# TASR1000.net
KiCad netlist of a schematic drawn in Altium Designer
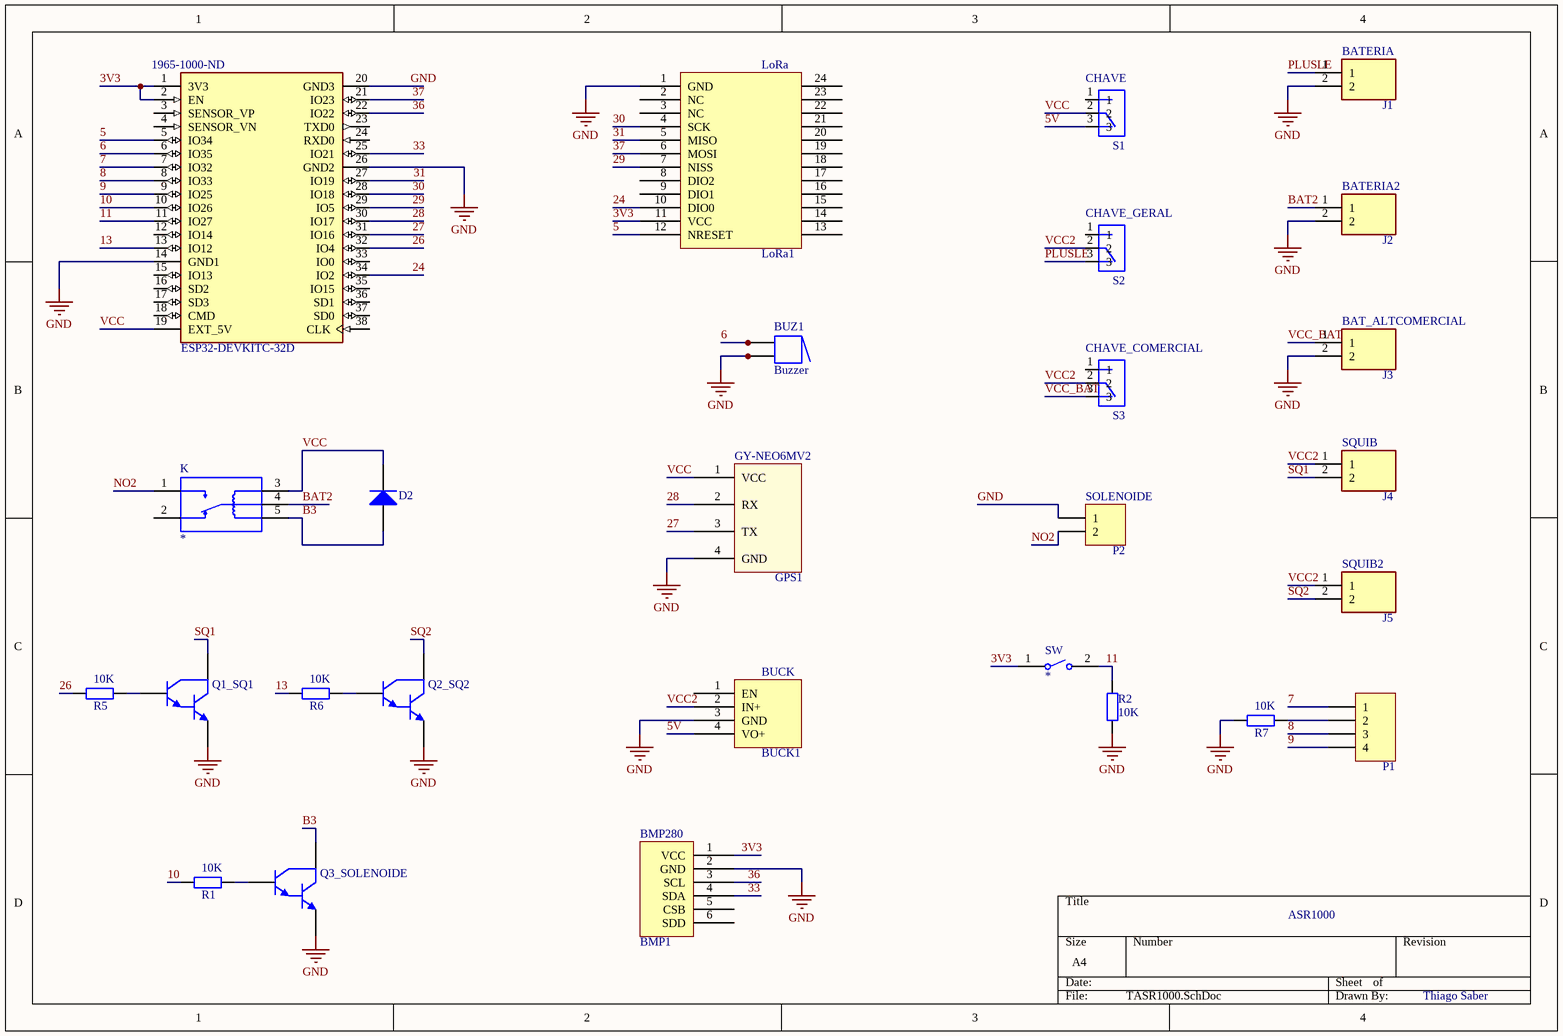
[diagram p0: TASR1000.SchDoc]

(export (version "E")
  (design (tool "Eeschema 10.0.6"))
  (components
    (comp (ref "BMP1")
      (value "BMP280")
      (footprint "BMP280")
      (description "BMP280 usado no projeto ASR1000.")
      (libsource (lib "BibliotecaASR1000") (part "BMP280"))
    )
    (comp (ref "BUCK1")
      (value "Buck")
      (footprint "BUCK")
      (description "Buck usado no projeto ASR1000.")
      (libsource (lib "BibliotecaASR1000") (part "Buck"))
    )
    (comp (ref "BUZ1")
      (value "Buzzer")
      (footprint "ABSM-1574")
      (description "Magnetic Transducer Buzzer")
      (fields (field (name "PUBLISHER") "Altium Limited"))
      (libsource (lib "Miscellaneous Devices") (part "Buzzer"))
    )
    (comp (ref "D2")
      (value "Diode 1N4001")
      (footprint "DO-41")
      (description "1 Amp General Purpose Rectifier")
      (fields (field (name "PUBLISHER") "Altium Limited"))
      (libsource (lib "Miscellaneous Devices") (part "Diode 1N4001"))
    )
    (comp (ref "GPS1")
      (value "Modulo GPS GY-NEO6MV2")
      (footprint "GY-NEO6MV2")
      (description "Modulo GPS utilizado no projeto ASR1000.")
      (fields (field (name "ALTIUM_UNNAMED_1") "GY-NEO6MV2"))
      (libsource (lib "GY-NEO6MV2") (part "GY-NEO6MV2"))
    )
    (comp (ref "J1")
      (value "BATERIA")
      (footprint "JST_B2B-XH-A(LF)(SN)")
      (description "Connector Header Through Hole 2 position 0.098 _2.50mm_")
      (fields (field (name "MP") "B2B-XH-A_LF__SN_") (field (name "MF") "JST Sales"))
      (libsource (lib "B2B-XH-A_LF__SN_") (part "B2B-XH-A(LF)(SN)"))
    )
    (comp (ref "J2")
      (value "BATERIA2")
      (footprint "JST_B2B-XH-A(LF)(SN)")
      (description "Connector Header Through Hole 2 position 0.098 _2.50mm_")
      (fields (field (name "MP") "B2B-XH-A_LF__SN_") (field (name "MF") "JST Sales"))
      (libsource (lib "B2B-XH-A_LF__SN_") (part "B2B-XH-A(LF)(SN)"))
    )
    (comp (ref "J3")
      (value "BAT_ALTCOMERCIAL")
      (footprint "JST_B2B-XH-A(LF)(SN)")
      (description "Connector Header Through Hole 2 position 0.098 _2.50mm_")
      (fields (field (name "MP") "B2B-XH-A_LF__SN_") (field (name "MF") "JST Sales"))
      (libsource (lib "B2B-XH-A_LF__SN_") (part "B2B-XH-A(LF)(SN)"))
    )
    (comp (ref "J4")
      (value "SQUIB")
      (footprint "JST_B2B-XH-A(LF)(SN)")
      (description "Connector Header Through Hole 2 position 0.098 _2.50mm_")
      (fields (field (name "MP") "B2B-XH-A_LF__SN_") (field (name "MF") "JST Sales"))
      (libsource (lib "B2B-XH-A_LF__SN_") (part "B2B-XH-A(LF)(SN)"))
    )
    (comp (ref "J5")
      (value "SQUIB2")
      (footprint "JST_B2B-XH-A(LF)(SN)")
      (description "Connector Header Through Hole 2 position 0.098 _2.50mm_")
      (fields (field (name "MP") "B2B-XH-A_LF__SN_") (field (name "MF") "JST Sales"))
      (libsource (lib "B2B-XH-A_LF__SN_") (part "B2B-XH-A(LF)(SN)"))
    )
    (comp (ref "K")
      (value "1-1721150-0")
      (footprint "RELAY_ORWH-SH-105D1F,000")
      (description "Electromechanical Relay 5VDC 15A SPDT __ 19.2mm 15.5mm 15mm__ THT General Purpose Relay")
      (fields
        (field (name "MP") "ORWH-SH-105D1F,000")
        (field (name "MF") "TE Connectivity")
        (field (name "COMMENT_1") "*")
      )
      (libsource (lib "ORWH-SH-105D1F_000") (part "ORWH-SH-105D1F,000"))
    )
    (comp (ref "LoRa1")
      (value "Modulo LoRa")
      (footprint "Suporte_Lora")
      (description "LoRa usado no projeto ASR1000.")
      (libsource (lib "BibliotecaASR1000") (part "Suporte Lora"))
    )
    (comp (ref "P1")
      (value "Header 4")
      (footprint "HDR1X4")
      (description "Header, 4-Pin")
      (fields (field (name "PUBLISHER") "Altium Limited"))
      (libsource (lib "Miscellaneous Connectors") (part "Header 4"))
    )
    (comp (ref "P2")
      (value "SOLENOIDE")
      (footprint "HDR1X2")
      (description "Header, 2-Pin")
      (fields (field (name "PUBLISHER") "Altium Limited"))
      (libsource (lib "Miscellaneous Connectors") (part "Header 2"))
    )
    (comp (ref "Q1_SQ1")
      (value "NPN1")
      (footprint "TO-92")
      (description "NPN Darlington Bipolar Transistor")
      (fields (field (name "PUBLISHER") "Altium Limited"))
      (libsource (lib "Miscellaneous Devices") (part "NPN1"))
    )
    (comp (ref "Q2_SQ2")
      (value "NPN1")
      (footprint "TO-92")
      (description "NPN Darlington Bipolar Transistor")
      (fields (field (name "PUBLISHER") "Altium Limited"))
      (libsource (lib "Miscellaneous Devices") (part "NPN1"))
    )
    (comp (ref "Q3_SOLENOIDE")
      (value "NPN1")
      (footprint "TO-92")
      (description "NPN Darlington Bipolar Transistor")
      (fields (field (name "PUBLISHER") "Altium Limited"))
      (libsource (lib "Miscellaneous Devices") (part "NPN1"))
    )
    (comp (ref "R1")
      (value "10K")
      (footprint "AXIAL-0.4")
      (description "Resistor")
      (fields (field (name "Comment") "Resistor de Q2_SQ2") (field (name "PUBLISHER") "Altium Limited"))
      (libsource (lib "Miscellaneous Devices") (part "Res2"))
    )
    (comp (ref "R2")
      (value "10K")
      (footprint "AXIAL-0.4")
      (description "Resistor")
      (fields
        (field (name "Comment") "Resistor do header de 4 pinos")
        (field (name "PUBLISHER") "Altium Limited")
      )
      (libsource (lib "") (part "Res2_1"))
    )
    (comp (ref "R5")
      (value "10K")
      (footprint "AXIAL-0.4")
      (description "Resistor")
      (fields (field (name "Comment") "Resistor de Q1_SQ1") (field (name "PUBLISHER") "Altium Limited"))
      (libsource (lib "Miscellaneous Devices") (part "Res2"))
    )
    (comp (ref "R6")
      (value "10K")
      (footprint "AXIAL-0.4")
      (description "Resistor")
      (fields (field (name "Comment") "Resistor de Q2_SQ2") (field (name "PUBLISHER") "Altium Limited"))
      (libsource (lib "Miscellaneous Devices") (part "Res2"))
    )
    (comp (ref "R7")
      (value "10K")
      (footprint "AXIAL-0.4")
      (description "Resistor")
      (fields
        (field (name "Comment") "Resistor do header de 4 pinos")
        (field (name "PUBLISHER") "Altium Limited")
      )
      (libsource (lib "Miscellaneous Devices") (part "Res2"))
    )
    (comp (ref "S1")
      (value "CHAVE")
      (footprint "SW_OS102011MS2QN1")
      (description "Slide Switch SPDT Through Hole")
      (fields (field (name "MF") "C&K") (field (name "MP") "OS102011MS2QN1"))
      (libsource (lib "OS102011MS2QN1") (part "OS102011MS2QN1"))
    )
    (comp (ref "S2")
      (value "CHAVE_GERAL")
      (footprint "SW_OS102011MS2QN1")
      (description "Slide Switch SPDT Through Hole")
      (fields (field (name "MF") "C&K") (field (name "MP") "OS102011MS2QN1"))
      (libsource (lib "OS102011MS2QN1") (part "OS102011MS2QN1"))
    )
    (comp (ref "S3")
      (value "CHAVE_COMERCIAL")
      (footprint "SW_OS102011MS2QN1")
      (description "Slide Switch SPDT Through Hole")
      (fields (field (name "MF") "C&K") (field (name "MP") "OS102011MS2QN1"))
      (libsource (lib "OS102011MS2QN1") (part "OS102011MS2QN1"))
    )
    (comp (ref "SW")
      (value "147694-1")
      (footprint "TE_FSM8JRT")
      (description "Switch Tactile OFF _ON_ SPST Round Button PC Pins 0.05A 12VDC 1.57N Thru-Hole Radial Tape")
      (fields
        (field (name "MF") "TE Connectivity")
        (field (name "MP") "FSM8JRT")
        (field (name "COMMENT_1") "*")
      )
      (libsource (lib "FSM8JRT") (part "FSM8JRT"))
    )
    (comp (ref "U")
      (value "ESP32-DEVKITC-32D")
      (footprint "MODULE_ESP32-DEVKITC-32D")
      (fields (field (name "MF") "Espressif Systems") (field (name "SUPPLIER PART NUMBER 1") "1965-1000-ND"))
      (libsource (lib "ESP32-DEVKITC-32D") (part "ESP32-DEVKITC-32D"))
    )
  )
  (nets
    (net (code "1") (name "/3V3") (class "Default")
      (node (ref "BMP1") (pin "1") (pinfunction "VCC_1") (pintype "passive"))
      (node (ref "LoRa1") (pin "11") (pinfunction "VCC_11") (pintype "passive"))
      (node (ref "SW") (pin "1") (pinfunction "1_1") (pintype "passive"))
      (node (ref "U") (pin "1") (pinfunction "3V3_1") (pintype "power_in"))
      (node (ref "U") (pin "2") (pinfunction "EN_2") (pintype "input"))
    )
    (net (code "2") (name "/5") (class "Default")
      (node (ref "LoRa1") (pin "12") (pinfunction "NRESET_12") (pintype "passive"))
      (node (ref "U") (pin "5") (pinfunction "IO34_5") (pintype "bidirectional"))
    )
    (net (code "3") (name "/5V") (class "Default")
      (node (ref "BUCK1") (pin "4") (pinfunction "VO+_4") (pintype "passive"))
      (node (ref "S1") (pin "3") (pinfunction "3_3") (pintype "passive"))
    )
    (net (code "4") (name "/6") (class "Default")
      (node (ref "BUZ1") (pin "1") (pinfunction "1_1") (pintype "passive"))
      (node (ref "BUZ1") (pin "1A") (pinfunction "1A_1A") (pintype "passive"))
      (node (ref "U") (pin "6") (pinfunction "IO35_6") (pintype "bidirectional"))
    )
    (net (code "5") (name "/7") (class "Default")
      (node (ref "P1") (pin "1") (pinfunction "1_1") (pintype "passive"))
      (node (ref "U") (pin "7") (pinfunction "IO32_7") (pintype "bidirectional"))
    )
    (net (code "6") (name "/8") (class "Default")
      (node (ref "P1") (pin "3") (pinfunction "3_3") (pintype "passive"))
      (node (ref "U") (pin "8") (pinfunction "IO33_8") (pintype "bidirectional"))
    )
    (net (code "7") (name "/9") (class "Default")
      (node (ref "P1") (pin "4") (pinfunction "4_4") (pintype "passive"))
      (node (ref "U") (pin "9") (pinfunction "IO25_9") (pintype "bidirectional"))
    )
    (net (code "8") (name "/10") (class "Default")
      (node (ref "R1") (pin "1") (pinfunction "1_1") (pintype "passive"))
      (node (ref "U") (pin "10") (pinfunction "IO26_10") (pintype "bidirectional"))
    )
    (net (code "9") (name "/11") (class "Default")
      (node (ref "R2") (pin "2") (pinfunction "2_2") (pintype "passive"))
      (node (ref "SW") (pin "2") (pinfunction "2_2") (pintype "passive"))
      (node (ref "U") (pin "11") (pinfunction "IO27_11") (pintype "bidirectional"))
    )
    (net (code "10") (name "/13") (class "Default")
      (node (ref "R6") (pin "1") (pinfunction "1_1") (pintype "passive"))
      (node (ref "U") (pin "13") (pinfunction "IO12_13") (pintype "bidirectional"))
    )
    (net (code "11") (name "/24") (class "Default")
      (node (ref "LoRa1") (pin "10") (pinfunction "DIO0_10") (pintype "passive"))
      (node (ref "U") (pin "34") (pinfunction "IO2_34") (pintype "bidirectional"))
    )
    (net (code "12") (name "/26") (class "Default")
      (node (ref "R5") (pin "1") (pinfunction "1_1") (pintype "passive"))
      (node (ref "U") (pin "32") (pinfunction "IO4_32") (pintype "bidirectional"))
    )
    (net (code "13") (name "/27") (class "Default")
      (node (ref "GPS1") (pin "3") (pinfunction "TX_3") (pintype "passive"))
      (node (ref "U") (pin "31") (pinfunction "IO16_31") (pintype "bidirectional"))
    )
    (net (code "14") (name "/28") (class "Default")
      (node (ref "GPS1") (pin "2") (pinfunction "RX_2") (pintype "passive"))
      (node (ref "U") (pin "30") (pinfunction "IO17_30") (pintype "bidirectional"))
    )
    (net (code "15") (name "/29") (class "Default")
      (node (ref "LoRa1") (pin "7") (pinfunction "NISS_7") (pintype "passive"))
      (node (ref "U") (pin "29") (pinfunction "IO5_29") (pintype "bidirectional"))
    )
    (net (code "16") (name "/30") (class "Default")
      (node (ref "LoRa1") (pin "4") (pinfunction "SCK_4") (pintype "passive"))
      (node (ref "U") (pin "28") (pinfunction "IO18_28") (pintype "bidirectional"))
    )
    (net (code "17") (name "/31") (class "Default")
      (node (ref "LoRa1") (pin "5") (pinfunction "MISO_5") (pintype "passive"))
      (node (ref "U") (pin "27") (pinfunction "IO19_27") (pintype "bidirectional"))
    )
    (net (code "18") (name "/33") (class "Default")
      (node (ref "BMP1") (pin "4") (pinfunction "SDA_4") (pintype "passive"))
      (node (ref "U") (pin "25") (pinfunction "IO21_25") (pintype "bidirectional"))
    )
    (net (code "19") (name "/36") (class "Default")
      (node (ref "BMP1") (pin "3") (pinfunction "SCL_3") (pintype "passive"))
      (node (ref "U") (pin "22") (pinfunction "IO22_22") (pintype "bidirectional"))
    )
    (net (code "20") (name "/37") (class "Default")
      (node (ref "LoRa1") (pin "6") (pinfunction "MOSI_6") (pintype "passive"))
      (node (ref "U") (pin "21") (pinfunction "IO23_21") (pintype "bidirectional"))
    )
    (net (code "21") (name "/B3") (class "Default")
      (node (ref "D2") (pin "1") (pinfunction "A_1") (pintype "passive"))
      (node (ref "K") (pin "5") (pinfunction "C2_5") (pintype "passive"))
      (node (ref "Q3_SOLENOIDE") (pin "1") (pinfunction "C_1") (pintype "passive"))
    )
    (net (code "22") (name "/BAT2") (class "Default")
      (node (ref "J2") (pin "1") (pinfunction "1_1") (pintype "passive"))
      (node (ref "K") (pin "4") (pinfunction "C_4") (pintype "passive"))
    )
    (net (code "23") (name "/NO2") (class "Default")
      (node (ref "K") (pin "1") (pinfunction "NO_1") (pintype "passive"))
      (node (ref "P2") (pin "2") (pinfunction "2_2") (pintype "passive"))
    )
    (net (code "24") (name "/PLUSLE") (class "Default")
      (node (ref "J1") (pin "1") (pinfunction "1_1") (pintype "passive"))
      (node (ref "S2") (pin "3") (pinfunction "3_3") (pintype "passive"))
    )
    (net (code "25") (name "/SQ1") (class "Default")
      (node (ref "J4") (pin "2") (pinfunction "2_2") (pintype "passive"))
      (node (ref "Q1_SQ1") (pin "1") (pinfunction "C_1") (pintype "passive"))
    )
    (net (code "26") (name "/SQ2") (class "Default")
      (node (ref "J5") (pin "2") (pinfunction "2_2") (pintype "passive"))
      (node (ref "Q2_SQ2") (pin "1") (pinfunction "C_1") (pintype "passive"))
    )
    (net (code "27") (name "/VCC") (class "Default")
      (node (ref "D2") (pin "2") (pinfunction "K_2") (pintype "passive"))
      (node (ref "GPS1") (pin "1") (pinfunction "VCC_1") (pintype "passive"))
      (node (ref "K") (pin "3") (pinfunction "C1_3") (pintype "passive"))
      (node (ref "S1") (pin "2") (pinfunction "2_2") (pintype "passive"))
      (node (ref "U") (pin "19") (pinfunction "EXT_5V_19") (pintype "power_in"))
    )
    (net (code "28") (name "/VCC2") (class "Default")
      (node (ref "BUCK1") (pin "2") (pinfunction "IN+_2") (pintype "passive"))
      (node (ref "J4") (pin "1") (pinfunction "1_1") (pintype "passive"))
      (node (ref "J5") (pin "1") (pinfunction "1_1") (pintype "passive"))
      (node (ref "S2") (pin "2") (pinfunction "2_2") (pintype "passive"))
      (node (ref "S3") (pin "2") (pinfunction "2_2") (pintype "passive"))
    )
    (net (code "29") (name "/VCC_BAT") (class "Default")
      (node (ref "J3") (pin "1") (pinfunction "1_1") (pintype "passive"))
      (node (ref "S3") (pin "3") (pinfunction "3_3") (pintype "passive"))
    )
    (net (code "30") (name "GND") (class "Default")
      (node (ref "BMP1") (pin "2") (pinfunction "GND_2") (pintype "passive"))
      (node (ref "BUCK1") (pin "3") (pinfunction "GND_3") (pintype "passive"))
      (node (ref "BUZ1") (pin "2") (pinfunction "2_2") (pintype "passive"))
      (node (ref "BUZ1") (pin "2A") (pinfunction "2A_2A") (pintype "passive"))
      (node (ref "GPS1") (pin "4") (pinfunction "GND_4") (pintype "passive"))
      (node (ref "J1") (pin "2") (pinfunction "2_2") (pintype "passive"))
      (node (ref "J2") (pin "2") (pinfunction "2_2") (pintype "passive"))
      (node (ref "J3") (pin "2") (pinfunction "2_2") (pintype "passive"))
      (node (ref "LoRa1") (pin "1") (pinfunction "GND_1") (pintype "passive"))
      (node (ref "P2") (pin "1") (pinfunction "1_1") (pintype "passive"))
      (node (ref "Q1_SQ1") (pin "3") (pinfunction "E_3") (pintype "passive"))
      (node (ref "Q2_SQ2") (pin "3") (pinfunction "E_3") (pintype "passive"))
      (node (ref "Q3_SOLENOIDE") (pin "3") (pinfunction "E_3") (pintype "passive"))
      (node (ref "R2") (pin "1") (pinfunction "1_1") (pintype "passive"))
      (node (ref "R7") (pin "1") (pinfunction "1_1") (pintype "passive"))
      (node (ref "U") (pin "14") (pinfunction "GND1_14") (pintype "power_in"))
      (node (ref "U") (pin "20") (pinfunction "GND3_20") (pintype "power_in"))
      (node (ref "U") (pin "26") (pinfunction "GND2_26") (pintype "power_in"))
    )
    (net (code "31") (name "Net-(P1-Pad2)") (class "Default")
      (node (ref "P1") (pin "2") (pinfunction "2_2") (pintype "passive"))
      (node (ref "R7") (pin "2") (pinfunction "2_2") (pintype "passive"))
    )
    (net (code "32") (name "Net-(Q1_SQ1-B)") (class "Default")
      (node (ref "Q1_SQ1") (pin "2") (pinfunction "B_2") (pintype "passive"))
      (node (ref "R5") (pin "2") (pinfunction "2_2") (pintype "passive"))
    )
    (net (code "33") (name "Net-(Q2_SQ2-B)") (class "Default")
      (node (ref "Q2_SQ2") (pin "2") (pinfunction "B_2") (pintype "passive"))
      (node (ref "R6") (pin "2") (pinfunction "2_2") (pintype "passive"))
    )
    (net (code "34") (name "Net-(Q3_SOLENOIDE-B)") (class "Default")
      (node (ref "Q3_SOLENOIDE") (pin "2") (pinfunction "B_2") (pintype "passive"))
      (node (ref "R1") (pin "2") (pinfunction "2_2") (pintype "passive"))
    )
    (net (code "35") (name "unconnected-(BMP1-CSB-Pad5)") (class "Default")
      (node (ref "BMP1") (pin "5") (pinfunction "CSB_5") (pintype "passive"))
    )
    (net (code "36") (name "unconnected-(BMP1-SDD-Pad6)") (class "Default")
      (node (ref "BMP1") (pin "6") (pinfunction "SDD_6") (pintype "passive"))
    )
    (net (code "37") (name "unconnected-(BUCK1-EN-Pad1)") (class "Default")
      (node (ref "BUCK1") (pin "1") (pinfunction "EN_1") (pintype "passive"))
    )
    (net (code "38") (name "unconnected-(K-NC-Pad2)") (class "Default")
      (node (ref "K") (pin "2") (pinfunction "NC_2") (pintype "passive"))
    )
    (net (code "39") (name "unconnected-(LoRa1-DIO1-Pad9)") (class "Default")
      (node (ref "LoRa1") (pin "9") (pinfunction "DIO1_9") (pintype "passive"))
    )
    (net (code "40") (name "unconnected-(LoRa1-DIO2-Pad8)") (class "Default")
      (node (ref "LoRa1") (pin "8") (pinfunction "DIO2_8") (pintype "passive"))
    )
    (net (code "41") (name "unconnected-(LoRa1-NC-Pad2)") (class "Default")
      (node (ref "LoRa1") (pin "2") (pinfunction "NC_2") (pintype "passive"))
    )
    (net (code "42") (name "unconnected-(LoRa1-NC-Pad3)") (class "Default")
      (node (ref "LoRa1") (pin "3") (pinfunction "NC_3") (pintype "passive"))
    )
    (net (code "43") (name "unconnected-(LoRa1-Pad13)") (class "Default")
      (node (ref "LoRa1") (pin "13") (pintype "passive"))
    )
    (net (code "44") (name "unconnected-(LoRa1-Pad14)") (class "Default")
      (node (ref "LoRa1") (pin "14") (pintype "passive"))
    )
    (net (code "45") (name "unconnected-(LoRa1-Pad15)") (class "Default")
      (node (ref "LoRa1") (pin "15") (pintype "passive"))
    )
    (net (code "46") (name "unconnected-(LoRa1-Pad16)") (class "Default")
      (node (ref "LoRa1") (pin "16") (pintype "passive"))
    )
    (net (code "47") (name "unconnected-(LoRa1-Pad17)") (class "Default")
      (node (ref "LoRa1") (pin "17") (pintype "passive"))
    )
    (net (code "48") (name "unconnected-(LoRa1-Pad18)") (class "Default")
      (node (ref "LoRa1") (pin "18") (pintype "passive"))
    )
    (net (code "49") (name "unconnected-(LoRa1-Pad19)") (class "Default")
      (node (ref "LoRa1") (pin "19") (pintype "passive"))
    )
    (net (code "50") (name "unconnected-(LoRa1-Pad20)") (class "Default")
      (node (ref "LoRa1") (pin "20") (pintype "passive"))
    )
    (net (code "51") (name "unconnected-(LoRa1-Pad21)") (class "Default")
      (node (ref "LoRa1") (pin "21") (pintype "passive"))
    )
    (net (code "52") (name "unconnected-(LoRa1-Pad22)") (class "Default")
      (node (ref "LoRa1") (pin "22") (pintype "passive"))
    )
    (net (code "53") (name "unconnected-(LoRa1-Pad23)") (class "Default")
      (node (ref "LoRa1") (pin "23") (pintype "passive"))
    )
    (net (code "54") (name "unconnected-(LoRa1-Pad24)") (class "Default")
      (node (ref "LoRa1") (pin "24") (pintype "passive"))
    )
    (net (code "55") (name "unconnected-(S1-Pad1)") (class "Default")
      (node (ref "S1") (pin "1") (pinfunction "1_1") (pintype "passive"))
    )
    (net (code "56") (name "unconnected-(S2-Pad1)") (class "Default")
      (node (ref "S2") (pin "1") (pinfunction "1_1") (pintype "passive"))
    )
    (net (code "57") (name "unconnected-(S3-Pad1)") (class "Default")
      (node (ref "S3") (pin "1") (pinfunction "1_1") (pintype "passive"))
    )
    (net (code "58") (name "unconnected-(U-CLK-Pad38)") (class "Default")
      (node (ref "U") (pin "38") (pinfunction "CLK_38") (pintype "input"))
    )
    (net (code "59") (name "unconnected-(U-CMD-Pad18)") (class "Default")
      (node (ref "U") (pin "18") (pinfunction "CMD_18") (pintype "bidirectional"))
    )
    (net (code "60") (name "unconnected-(U-IO0-Pad33)") (class "Default")
      (node (ref "U") (pin "33") (pinfunction "IO0_33") (pintype "bidirectional"))
    )
    (net (code "61") (name "unconnected-(U-IO13-Pad15)") (class "Default")
      (node (ref "U") (pin "15") (pinfunction "IO13_15") (pintype "bidirectional"))
    )
    (net (code "62") (name "unconnected-(U-IO14-Pad12)") (class "Default")
      (node (ref "U") (pin "12") (pinfunction "IO14_12") (pintype "bidirectional"))
    )
    (net (code "63") (name "unconnected-(U-IO15-Pad35)") (class "Default")
      (node (ref "U") (pin "35") (pinfunction "IO15_35") (pintype "bidirectional"))
    )
    (net (code "64") (name "unconnected-(U-RXD0-Pad24)") (class "Default")
      (node (ref "U") (pin "24") (pinfunction "RXD0_24") (pintype "input"))
    )
    (net (code "65") (name "unconnected-(U-SD0-Pad37)") (class "Default")
      (node (ref "U") (pin "37") (pinfunction "SD0_37") (pintype "bidirectional"))
    )
    (net (code "66") (name "unconnected-(U-SD1-Pad36)") (class "Default")
      (node (ref "U") (pin "36") (pinfunction "SD1_36") (pintype "bidirectional"))
    )
    (net (code "67") (name "unconnected-(U-SD2-Pad16)") (class "Default")
      (node (ref "U") (pin "16") (pinfunction "SD2_16") (pintype "bidirectional"))
    )
    (net (code "68") (name "unconnected-(U-SD3-Pad17)") (class "Default")
      (node (ref "U") (pin "17") (pinfunction "SD3_17") (pintype "bidirectional"))
    )
    (net (code "69") (name "unconnected-(U-SENSOR_VN-Pad4)") (class "Default")
      (node (ref "U") (pin "4") (pinfunction "SENSOR_VN_4") (pintype "input"))
    )
    (net (code "70") (name "unconnected-(U-SENSOR_VP-Pad3)") (class "Default")
      (node (ref "U") (pin "3") (pinfunction "SENSOR_VP_3") (pintype "input"))
    )
    (net (code "71") (name "unconnected-(U-TXD0-Pad23)") (class "Default")
      (node (ref "U") (pin "23") (pinfunction "TXD0_23") (pintype "output"))
    )
  )
)
